# Digital_Outputs.net
KiCad netlist of a schematic drawn in Altium Designer
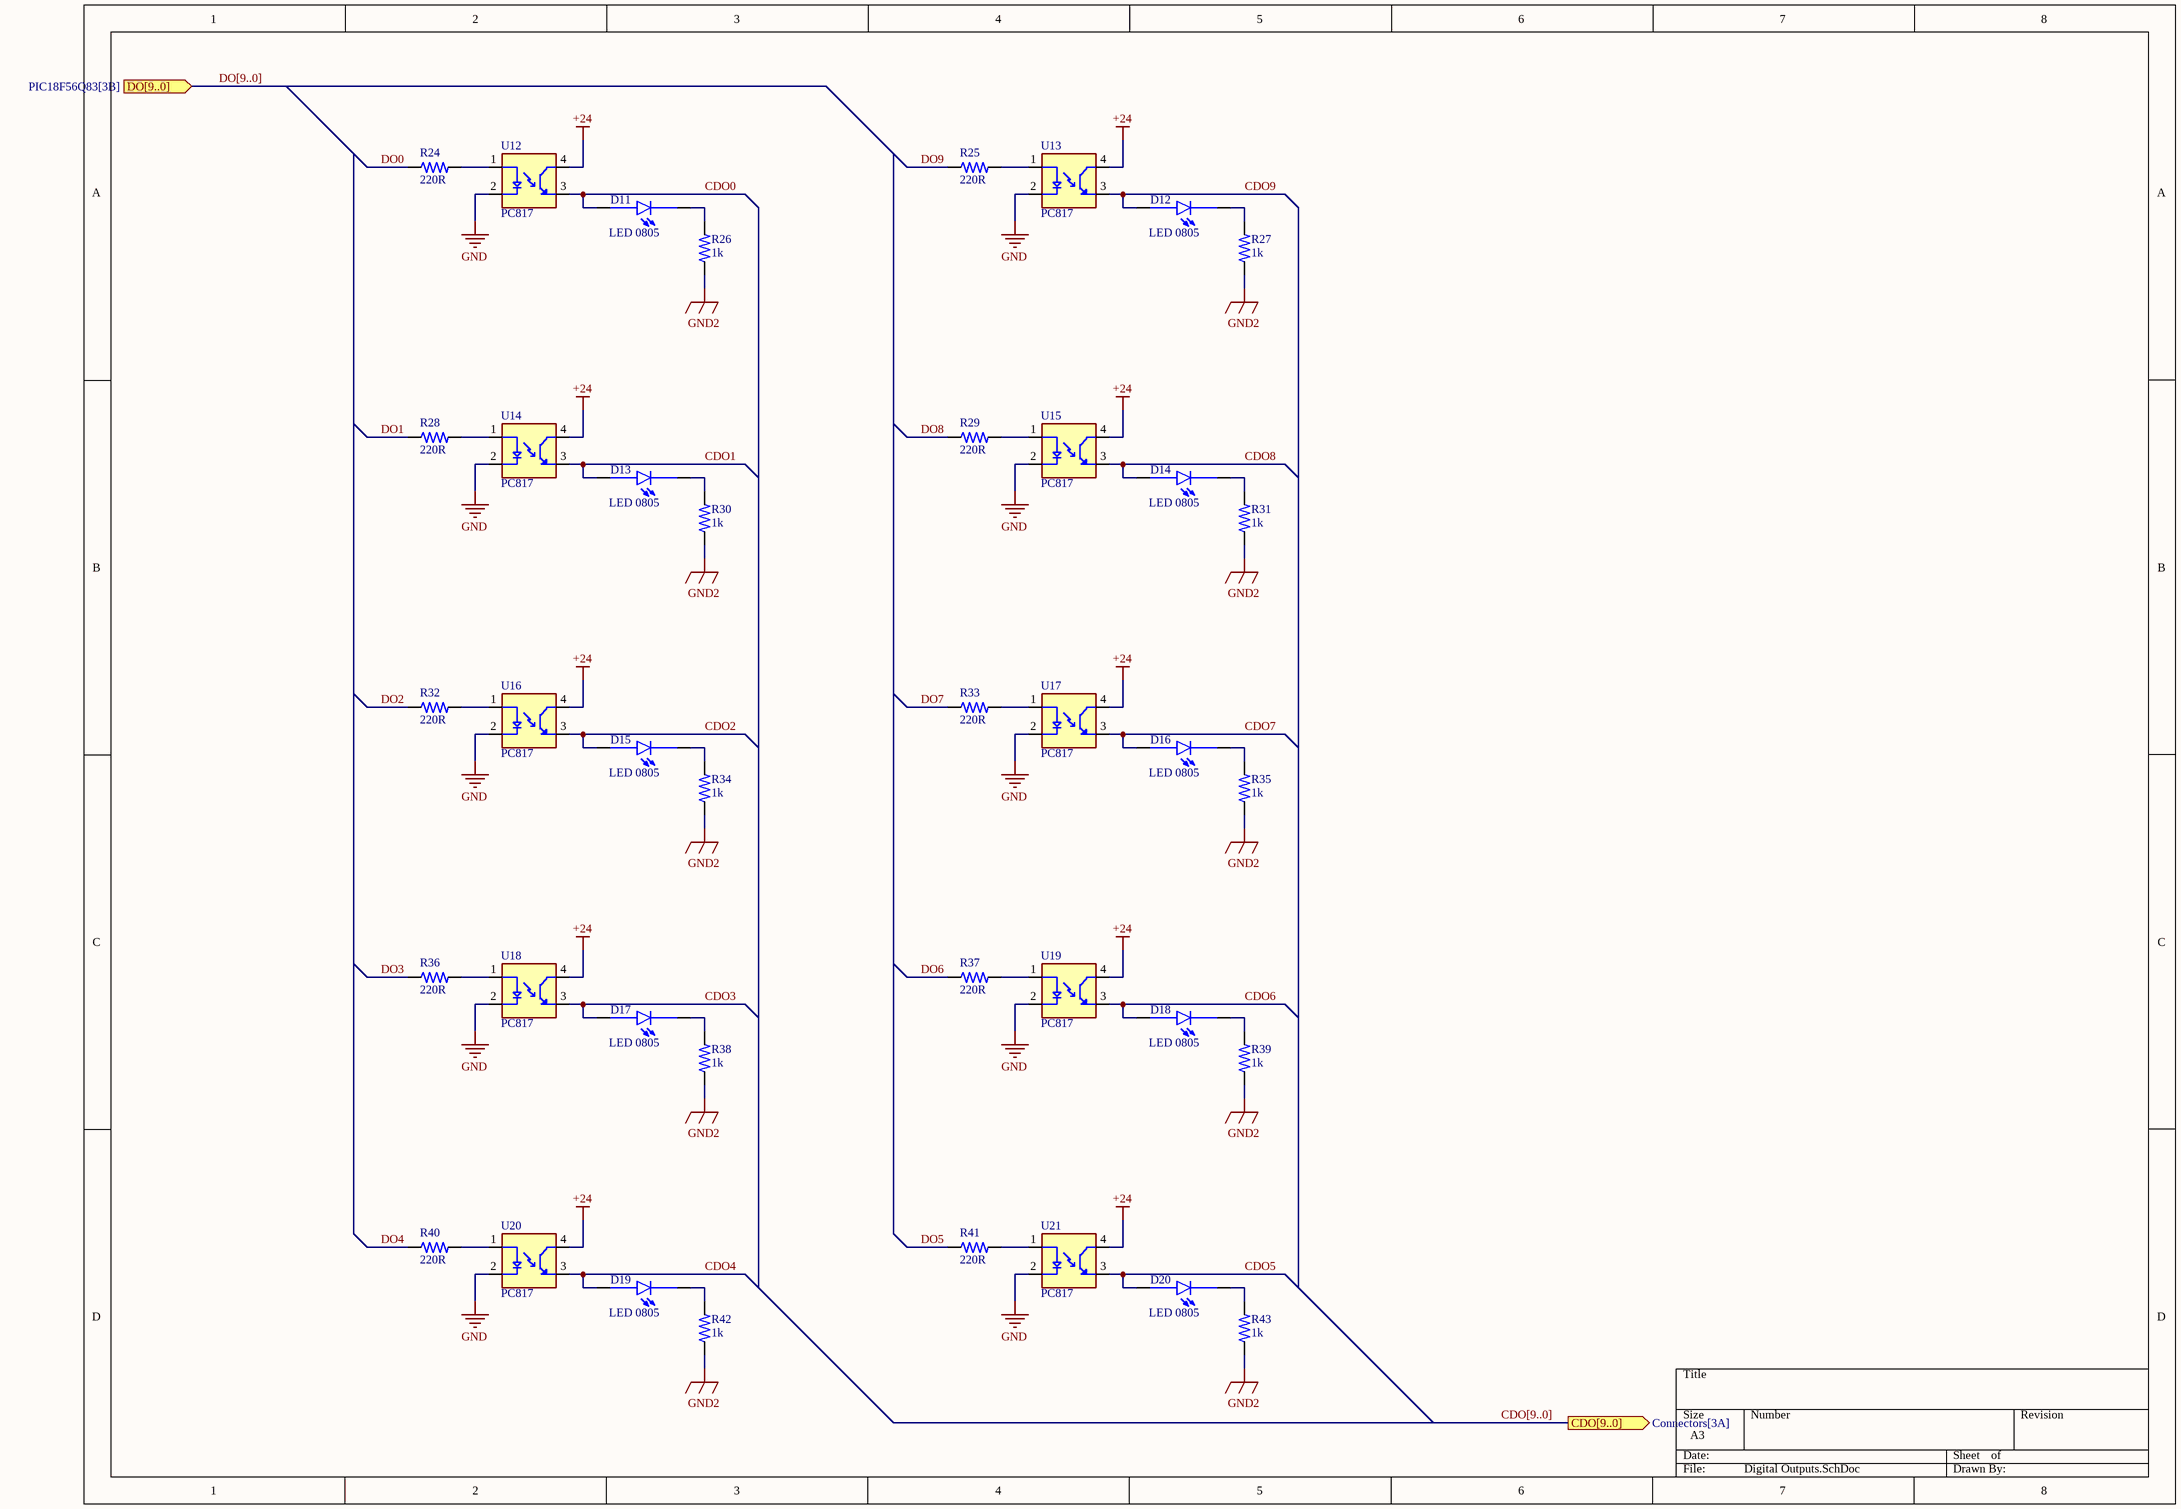
[diagram p0: Digital Outputs.SchDoc]

(export (version "E")
  (design (tool "Eeschema 10.0.6"))
  (components
    (comp (ref "D11")
      (value "LED 0805")
      (footprint "LED 0805")
      (description "LED Uni-Color Green 4-Pin Chip 0805 T/R")
      (fields (field (name "MP") "597-3305-607F"))
      (libsource (lib "LEDs SMD") (part "LED 0805"))
    )
    (comp (ref "D12")
      (value "LED 0805")
      (footprint "LED 0805")
      (description "LED Uni-Color Green 4-Pin Chip 0805 T/R")
      (fields (field (name "MP") "597-3305-607F"))
      (libsource (lib "LEDs SMD") (part "LED 0805"))
    )
    (comp (ref "D13")
      (value "LED 0805")
      (footprint "LED 0805")
      (description "LED Uni-Color Green 4-Pin Chip 0805 T/R")
      (fields (field (name "MP") "597-3305-607F"))
      (libsource (lib "LEDs SMD") (part "LED 0805"))
    )
    (comp (ref "D14")
      (value "LED 0805")
      (footprint "LED 0805")
      (description "LED Uni-Color Green 4-Pin Chip 0805 T/R")
      (fields (field (name "MP") "597-3305-607F"))
      (libsource (lib "LEDs SMD") (part "LED 0805"))
    )
    (comp (ref "D15")
      (value "LED 0805")
      (footprint "LED 0805")
      (description "LED Uni-Color Green 4-Pin Chip 0805 T/R")
      (fields (field (name "MP") "597-3305-607F"))
      (libsource (lib "LEDs SMD") (part "LED 0805"))
    )
    (comp (ref "D16")
      (value "LED 0805")
      (footprint "LED 0805")
      (description "LED Uni-Color Green 4-Pin Chip 0805 T/R")
      (fields (field (name "MP") "597-3305-607F"))
      (libsource (lib "LEDs SMD") (part "LED 0805"))
    )
    (comp (ref "D17")
      (value "LED 0805")
      (footprint "LED 0805")
      (description "LED Uni-Color Green 4-Pin Chip 0805 T/R")
      (fields (field (name "MP") "597-3305-607F"))
      (libsource (lib "LEDs SMD") (part "LED 0805"))
    )
    (comp (ref "D18")
      (value "LED 0805")
      (footprint "LED 0805")
      (description "LED Uni-Color Green 4-Pin Chip 0805 T/R")
      (fields (field (name "MP") "597-3305-607F"))
      (libsource (lib "LEDs SMD") (part "LED 0805"))
    )
    (comp (ref "D19")
      (value "LED 0805")
      (footprint "LED 0805")
      (description "LED Uni-Color Green 4-Pin Chip 0805 T/R")
      (fields (field (name "MP") "597-3305-607F"))
      (libsource (lib "LEDs SMD") (part "LED 0805"))
    )
    (comp (ref "D20")
      (value "LED 0805")
      (footprint "LED 0805")
      (description "LED Uni-Color Green 4-Pin Chip 0805 T/R")
      (fields (field (name "MP") "597-3305-607F"))
      (libsource (lib "LEDs SMD") (part "LED 0805"))
    )
    (comp (ref "R24")
      (value "220R")
      (footprint "0805")
      (fields
        (field (name "MP") "2-2176053-0")
        (field (name "TOLERANCE") "1%")
        (field (name "MF") "TE Connectivity")
      )
      (libsource (lib "Resistors SMD") (part "0805_Resistor"))
    )
    (comp (ref "R25")
      (value "220R")
      (footprint "0805")
      (fields
        (field (name "MP") "2-2176053-0")
        (field (name "TOLERANCE") "1%")
        (field (name "MF") "TE Connectivity")
      )
      (libsource (lib "Resistors SMD") (part "0805_Resistor"))
    )
    (comp (ref "R26")
      (value "1k")
      (footprint "0805")
      (fields
        (field (name "MP") "2-2176053-0")
        (field (name "TOLERANCE") "1%")
        (field (name "MF") "TE Connectivity")
      )
      (libsource (lib "Resistors SMD") (part "0805_Resistor"))
    )
    (comp (ref "R27")
      (value "1k")
      (footprint "0805")
      (fields
        (field (name "MP") "2-2176053-0")
        (field (name "TOLERANCE") "1%")
        (field (name "MF") "TE Connectivity")
      )
      (libsource (lib "Resistors SMD") (part "0805_Resistor"))
    )
    (comp (ref "R28")
      (value "220R")
      (footprint "0805")
      (fields
        (field (name "MP") "2-2176053-0")
        (field (name "TOLERANCE") "1%")
        (field (name "MF") "TE Connectivity")
      )
      (libsource (lib "Resistors SMD") (part "0805_Resistor"))
    )
    (comp (ref "R29")
      (value "220R")
      (footprint "0805")
      (fields
        (field (name "MP") "2-2176053-0")
        (field (name "TOLERANCE") "1%")
        (field (name "MF") "TE Connectivity")
      )
      (libsource (lib "Resistors SMD") (part "0805_Resistor"))
    )
    (comp (ref "R30")
      (value "1k")
      (footprint "0805")
      (fields
        (field (name "MP") "2-2176053-0")
        (field (name "TOLERANCE") "1%")
        (field (name "MF") "TE Connectivity")
      )
      (libsource (lib "Resistors SMD") (part "0805_Resistor"))
    )
    (comp (ref "R31")
      (value "1k")
      (footprint "0805")
      (fields
        (field (name "MP") "2-2176053-0")
        (field (name "TOLERANCE") "1%")
        (field (name "MF") "TE Connectivity")
      )
      (libsource (lib "Resistors SMD") (part "0805_Resistor"))
    )
    (comp (ref "R32")
      (value "220R")
      (footprint "0805")
      (fields
        (field (name "MP") "2-2176053-0")
        (field (name "TOLERANCE") "1%")
        (field (name "MF") "TE Connectivity")
      )
      (libsource (lib "Resistors SMD") (part "0805_Resistor"))
    )
    (comp (ref "R33")
      (value "220R")
      (footprint "0805")
      (fields
        (field (name "MP") "2-2176053-0")
        (field (name "TOLERANCE") "1%")
        (field (name "MF") "TE Connectivity")
      )
      (libsource (lib "Resistors SMD") (part "0805_Resistor"))
    )
    (comp (ref "R34")
      (value "1k")
      (footprint "0805")
      (fields
        (field (name "MP") "2-2176053-0")
        (field (name "TOLERANCE") "1%")
        (field (name "MF") "TE Connectivity")
      )
      (libsource (lib "Resistors SMD") (part "0805_Resistor"))
    )
    (comp (ref "R35")
      (value "1k")
      (footprint "0805")
      (fields
        (field (name "MP") "2-2176053-0")
        (field (name "TOLERANCE") "1%")
        (field (name "MF") "TE Connectivity")
      )
      (libsource (lib "Resistors SMD") (part "0805_Resistor"))
    )
    (comp (ref "R36")
      (value "220R")
      (footprint "0805")
      (fields
        (field (name "MP") "2-2176053-0")
        (field (name "TOLERANCE") "1%")
        (field (name "MF") "TE Connectivity")
      )
      (libsource (lib "Resistors SMD") (part "0805_Resistor"))
    )
    (comp (ref "R37")
      (value "220R")
      (footprint "0805")
      (fields
        (field (name "MP") "2-2176053-0")
        (field (name "TOLERANCE") "1%")
        (field (name "MF") "TE Connectivity")
      )
      (libsource (lib "Resistors SMD") (part "0805_Resistor"))
    )
    (comp (ref "R38")
      (value "1k")
      (footprint "0805")
      (fields
        (field (name "MP") "2-2176053-0")
        (field (name "TOLERANCE") "1%")
        (field (name "MF") "TE Connectivity")
      )
      (libsource (lib "Resistors SMD") (part "0805_Resistor"))
    )
    (comp (ref "R39")
      (value "1k")
      (footprint "0805")
      (fields
        (field (name "MP") "2-2176053-0")
        (field (name "TOLERANCE") "1%")
        (field (name "MF") "TE Connectivity")
      )
      (libsource (lib "Resistors SMD") (part "0805_Resistor"))
    )
    (comp (ref "R40")
      (value "220R")
      (footprint "0805")
      (fields
        (field (name "MP") "2-2176053-0")
        (field (name "TOLERANCE") "1%")
        (field (name "MF") "TE Connectivity")
      )
      (libsource (lib "Resistors SMD") (part "0805_Resistor"))
    )
    (comp (ref "R41")
      (value "220R")
      (footprint "0805")
      (fields
        (field (name "MP") "2-2176053-0")
        (field (name "TOLERANCE") "1%")
        (field (name "MF") "TE Connectivity")
      )
      (libsource (lib "Resistors SMD") (part "0805_Resistor"))
    )
    (comp (ref "R42")
      (value "1k")
      (footprint "0805")
      (fields
        (field (name "MP") "2-2176053-0")
        (field (name "TOLERANCE") "1%")
        (field (name "MF") "TE Connectivity")
      )
      (libsource (lib "Resistors SMD") (part "0805_Resistor"))
    )
    (comp (ref "R43")
      (value "1k")
      (footprint "0805")
      (fields
        (field (name "MP") "2-2176053-0")
        (field (name "TOLERANCE") "1%")
        (field (name "MF") "TE Connectivity")
      )
      (libsource (lib "Resistors SMD") (part "0805_Resistor"))
    )
    (comp (ref "U12")
      (value "PC817")
      (footprint "PC817")
      (description "Optoisolator Transistor Output 5000Vrms 1 Channel 4-SMD")
      (fields (field (name "MP") "PC817XI") (field (name "MF") "Sharp Microelectronics"))
      (libsource (lib "Optocoupler SMD") (part "PC817"))
    )
    (comp (ref "U13")
      (value "PC817")
      (footprint "PC817")
      (description "Optoisolator Transistor Output 5000Vrms 1 Channel 4-SMD")
      (fields (field (name "MP") "PC817XI") (field (name "MF") "Sharp Microelectronics"))
      (libsource (lib "Optocoupler SMD") (part "PC817"))
    )
    (comp (ref "U14")
      (value "PC817")
      (footprint "PC817")
      (description "Optoisolator Transistor Output 5000Vrms 1 Channel 4-SMD")
      (fields (field (name "MP") "PC817XI") (field (name "MF") "Sharp Microelectronics"))
      (libsource (lib "Optocoupler SMD") (part "PC817"))
    )
    (comp (ref "U15")
      (value "PC817")
      (footprint "PC817")
      (description "Optoisolator Transistor Output 5000Vrms 1 Channel 4-SMD")
      (fields (field (name "MP") "PC817XI") (field (name "MF") "Sharp Microelectronics"))
      (libsource (lib "Optocoupler SMD") (part "PC817"))
    )
    (comp (ref "U16")
      (value "PC817")
      (footprint "PC817")
      (description "Optoisolator Transistor Output 5000Vrms 1 Channel 4-SMD")
      (fields (field (name "MP") "PC817XI") (field (name "MF") "Sharp Microelectronics"))
      (libsource (lib "Optocoupler SMD") (part "PC817"))
    )
    (comp (ref "U17")
      (value "PC817")
      (footprint "PC817")
      (description "Optoisolator Transistor Output 5000Vrms 1 Channel 4-SMD")
      (fields (field (name "MP") "PC817XI") (field (name "MF") "Sharp Microelectronics"))
      (libsource (lib "Optocoupler SMD") (part "PC817"))
    )
    (comp (ref "U18")
      (value "PC817")
      (footprint "PC817")
      (description "Optoisolator Transistor Output 5000Vrms 1 Channel 4-SMD")
      (fields (field (name "MP") "PC817XI") (field (name "MF") "Sharp Microelectronics"))
      (libsource (lib "Optocoupler SMD") (part "PC817"))
    )
    (comp (ref "U19")
      (value "PC817")
      (footprint "PC817")
      (description "Optoisolator Transistor Output 5000Vrms 1 Channel 4-SMD")
      (fields (field (name "MP") "PC817XI") (field (name "MF") "Sharp Microelectronics"))
      (libsource (lib "Optocoupler SMD") (part "PC817"))
    )
    (comp (ref "U20")
      (value "PC817")
      (footprint "PC817")
      (description "Optoisolator Transistor Output 5000Vrms 1 Channel 4-SMD")
      (fields (field (name "MP") "PC817XI") (field (name "MF") "Sharp Microelectronics"))
      (libsource (lib "Optocoupler SMD") (part "PC817"))
    )
    (comp (ref "U21")
      (value "PC817")
      (footprint "PC817")
      (description "Optoisolator Transistor Output 5000Vrms 1 Channel 4-SMD")
      (fields (field (name "MP") "PC817XI") (field (name "MF") "Sharp Microelectronics"))
      (libsource (lib "Optocoupler SMD") (part "PC817"))
    )
  )
  (nets
    (net (code "1") (name "+24") (class "Default")
      (node (ref "U12") (pin "4") (pinfunction "CT_4") (pintype "passive"))
      (node (ref "U13") (pin "4") (pinfunction "CT_4") (pintype "passive"))
      (node (ref "U14") (pin "4") (pinfunction "CT_4") (pintype "passive"))
      (node (ref "U15") (pin "4") (pinfunction "CT_4") (pintype "passive"))
      (node (ref "U16") (pin "4") (pinfunction "CT_4") (pintype "passive"))
      (node (ref "U17") (pin "4") (pinfunction "CT_4") (pintype "passive"))
      (node (ref "U18") (pin "4") (pinfunction "CT_4") (pintype "passive"))
      (node (ref "U19") (pin "4") (pinfunction "CT_4") (pintype "passive"))
      (node (ref "U20") (pin "4") (pinfunction "CT_4") (pintype "passive"))
      (node (ref "U21") (pin "4") (pinfunction "CT_4") (pintype "passive"))
    )
    (net (code "2") (name "/CDO0") (class "Default")
      (node (ref "D11") (pin "A") (pinfunction "A_A") (pintype "passive"))
      (node (ref "U12") (pin "3") (pinfunction "ET_3") (pintype "passive"))
    )
    (net (code "3") (name "/CDO1") (class "Default")
      (node (ref "D13") (pin "A") (pinfunction "A_A") (pintype "passive"))
      (node (ref "U14") (pin "3") (pinfunction "ET_3") (pintype "passive"))
    )
    (net (code "4") (name "/CDO2") (class "Default")
      (node (ref "D15") (pin "A") (pinfunction "A_A") (pintype "passive"))
      (node (ref "U16") (pin "3") (pinfunction "ET_3") (pintype "passive"))
    )
    (net (code "5") (name "/CDO3") (class "Default")
      (node (ref "D17") (pin "A") (pinfunction "A_A") (pintype "passive"))
      (node (ref "U18") (pin "3") (pinfunction "ET_3") (pintype "passive"))
    )
    (net (code "6") (name "/CDO4") (class "Default")
      (node (ref "D19") (pin "A") (pinfunction "A_A") (pintype "passive"))
      (node (ref "U20") (pin "3") (pinfunction "ET_3") (pintype "passive"))
    )
    (net (code "7") (name "/CDO5") (class "Default")
      (node (ref "D20") (pin "A") (pinfunction "A_A") (pintype "passive"))
      (node (ref "U21") (pin "3") (pinfunction "ET_3") (pintype "passive"))
    )
    (net (code "8") (name "/CDO6") (class "Default")
      (node (ref "D18") (pin "A") (pinfunction "A_A") (pintype "passive"))
      (node (ref "U19") (pin "3") (pinfunction "ET_3") (pintype "passive"))
    )
    (net (code "9") (name "/CDO7") (class "Default")
      (node (ref "D16") (pin "A") (pinfunction "A_A") (pintype "passive"))
      (node (ref "U17") (pin "3") (pinfunction "ET_3") (pintype "passive"))
    )
    (net (code "10") (name "/CDO8") (class "Default")
      (node (ref "D14") (pin "A") (pinfunction "A_A") (pintype "passive"))
      (node (ref "U15") (pin "3") (pinfunction "ET_3") (pintype "passive"))
    )
    (net (code "11") (name "/CDO9") (class "Default")
      (node (ref "D12") (pin "A") (pinfunction "A_A") (pintype "passive"))
      (node (ref "U13") (pin "3") (pinfunction "ET_3") (pintype "passive"))
    )
    (net (code "13") (name "/DO0") (class "Default")
      (node (ref "R24") (pin "1") (pinfunction "1_1") (pintype "passive"))
    )
    (net (code "14") (name "/DO1") (class "Default")
      (node (ref "R28") (pin "1") (pinfunction "1_1") (pintype "passive"))
    )
    (net (code "15") (name "/DO2") (class "Default")
      (node (ref "R32") (pin "1") (pinfunction "1_1") (pintype "passive"))
    )
    (net (code "16") (name "/DO3") (class "Default")
      (node (ref "R36") (pin "1") (pinfunction "1_1") (pintype "passive"))
    )
    (net (code "17") (name "/DO4") (class "Default")
      (node (ref "R40") (pin "1") (pinfunction "1_1") (pintype "passive"))
    )
    (net (code "18") (name "/DO5") (class "Default")
      (node (ref "R41") (pin "1") (pinfunction "1_1") (pintype "passive"))
    )
    (net (code "19") (name "/DO6") (class "Default")
      (node (ref "R37") (pin "1") (pinfunction "1_1") (pintype "passive"))
    )
    (net (code "20") (name "/DO7") (class "Default")
      (node (ref "R33") (pin "1") (pinfunction "1_1") (pintype "passive"))
    )
    (net (code "21") (name "/DO8") (class "Default")
      (node (ref "R29") (pin "1") (pinfunction "1_1") (pintype "passive"))
    )
    (net (code "22") (name "/DO9") (class "Default")
      (node (ref "R25") (pin "1") (pinfunction "1_1") (pintype "passive"))
    )
    (net (code "24") (name "GND") (class "Default")
      (node (ref "U12") (pin "2") (pinfunction "C_2") (pintype "passive"))
      (node (ref "U13") (pin "2") (pinfunction "C_2") (pintype "passive"))
      (node (ref "U14") (pin "2") (pinfunction "C_2") (pintype "passive"))
      (node (ref "U15") (pin "2") (pinfunction "C_2") (pintype "passive"))
      (node (ref "U16") (pin "2") (pinfunction "C_2") (pintype "passive"))
      (node (ref "U17") (pin "2") (pinfunction "C_2") (pintype "passive"))
      (node (ref "U18") (pin "2") (pinfunction "C_2") (pintype "passive"))
      (node (ref "U19") (pin "2") (pinfunction "C_2") (pintype "passive"))
      (node (ref "U20") (pin "2") (pinfunction "C_2") (pintype "passive"))
      (node (ref "U21") (pin "2") (pinfunction "C_2") (pintype "passive"))
    )
    (net (code "25") (name "GND2") (class "Default")
      (node (ref "R26") (pin "1") (pinfunction "1_1") (pintype "passive"))
      (node (ref "R27") (pin "1") (pinfunction "1_1") (pintype "passive"))
      (node (ref "R30") (pin "1") (pinfunction "1_1") (pintype "passive"))
      (node (ref "R31") (pin "1") (pinfunction "1_1") (pintype "passive"))
      (node (ref "R34") (pin "1") (pinfunction "1_1") (pintype "passive"))
      (node (ref "R35") (pin "1") (pinfunction "1_1") (pintype "passive"))
      (node (ref "R38") (pin "1") (pinfunction "1_1") (pintype "passive"))
      (node (ref "R39") (pin "1") (pinfunction "1_1") (pintype "passive"))
      (node (ref "R42") (pin "1") (pinfunction "1_1") (pintype "passive"))
      (node (ref "R43") (pin "1") (pinfunction "1_1") (pintype "passive"))
    )
    (net (code "26") (name "Net-(D11-PadC)") (class "Default")
      (node (ref "D11") (pin "C") (pinfunction "C_C") (pintype "passive"))
      (node (ref "R26") (pin "2") (pinfunction "2_2") (pintype "passive"))
    )
    (net (code "27") (name "Net-(D12-PadC)") (class "Default")
      (node (ref "D12") (pin "C") (pinfunction "C_C") (pintype "passive"))
      (node (ref "R27") (pin "2") (pinfunction "2_2") (pintype "passive"))
    )
    (net (code "28") (name "Net-(D13-PadC)") (class "Default")
      (node (ref "D13") (pin "C") (pinfunction "C_C") (pintype "passive"))
      (node (ref "R30") (pin "2") (pinfunction "2_2") (pintype "passive"))
    )
    (net (code "29") (name "Net-(D14-PadC)") (class "Default")
      (node (ref "D14") (pin "C") (pinfunction "C_C") (pintype "passive"))
      (node (ref "R31") (pin "2") (pinfunction "2_2") (pintype "passive"))
    )
    (net (code "30") (name "Net-(D15-PadC)") (class "Default")
      (node (ref "D15") (pin "C") (pinfunction "C_C") (pintype "passive"))
      (node (ref "R34") (pin "2") (pinfunction "2_2") (pintype "passive"))
    )
    (net (code "31") (name "Net-(D16-PadC)") (class "Default")
      (node (ref "D16") (pin "C") (pinfunction "C_C") (pintype "passive"))
      (node (ref "R35") (pin "2") (pinfunction "2_2") (pintype "passive"))
    )
    (net (code "32") (name "Net-(D17-PadC)") (class "Default")
      (node (ref "D17") (pin "C") (pinfunction "C_C") (pintype "passive"))
      (node (ref "R38") (pin "2") (pinfunction "2_2") (pintype "passive"))
    )
    (net (code "33") (name "Net-(D18-PadC)") (class "Default")
      (node (ref "D18") (pin "C") (pinfunction "C_C") (pintype "passive"))
      (node (ref "R39") (pin "2") (pinfunction "2_2") (pintype "passive"))
    )
    (net (code "34") (name "Net-(D19-PadC)") (class "Default")
      (node (ref "D19") (pin "C") (pinfunction "C_C") (pintype "passive"))
      (node (ref "R42") (pin "2") (pinfunction "2_2") (pintype "passive"))
    )
    (net (code "35") (name "Net-(D20-PadC)") (class "Default")
      (node (ref "D20") (pin "C") (pinfunction "C_C") (pintype "passive"))
      (node (ref "R43") (pin "2") (pinfunction "2_2") (pintype "passive"))
    )
    (net (code "36") (name "Net-(U12-A)") (class "Default")
      (node (ref "R24") (pin "2") (pinfunction "2_2") (pintype "passive"))
      (node (ref "U12") (pin "1") (pinfunction "A_1") (pintype "passive"))
    )
    (net (code "37") (name "Net-(U13-A)") (class "Default")
      (node (ref "R25") (pin "2") (pinfunction "2_2") (pintype "passive"))
      (node (ref "U13") (pin "1") (pinfunction "A_1") (pintype "passive"))
    )
    (net (code "38") (name "Net-(U14-A)") (class "Default")
      (node (ref "R28") (pin "2") (pinfunction "2_2") (pintype "passive"))
      (node (ref "U14") (pin "1") (pinfunction "A_1") (pintype "passive"))
    )
    (net (code "39") (name "Net-(U15-A)") (class "Default")
      (node (ref "R29") (pin "2") (pinfunction "2_2") (pintype "passive"))
      (node (ref "U15") (pin "1") (pinfunction "A_1") (pintype "passive"))
    )
    (net (code "40") (name "Net-(U16-A)") (class "Default")
      (node (ref "R32") (pin "2") (pinfunction "2_2") (pintype "passive"))
      (node (ref "U16") (pin "1") (pinfunction "A_1") (pintype "passive"))
    )
    (net (code "41") (name "Net-(U17-A)") (class "Default")
      (node (ref "R33") (pin "2") (pinfunction "2_2") (pintype "passive"))
      (node (ref "U17") (pin "1") (pinfunction "A_1") (pintype "passive"))
    )
    (net (code "42") (name "Net-(U18-A)") (class "Default")
      (node (ref "R36") (pin "2") (pinfunction "2_2") (pintype "passive"))
      (node (ref "U18") (pin "1") (pinfunction "A_1") (pintype "passive"))
    )
    (net (code "43") (name "Net-(U19-A)") (class "Default")
      (node (ref "R37") (pin "2") (pinfunction "2_2") (pintype "passive"))
      (node (ref "U19") (pin "1") (pinfunction "A_1") (pintype "passive"))
    )
    (net (code "44") (name "Net-(U20-A)") (class "Default")
      (node (ref "R40") (pin "2") (pinfunction "2_2") (pintype "passive"))
      (node (ref "U20") (pin "1") (pinfunction "A_1") (pintype "passive"))
    )
    (net (code "45") (name "Net-(U21-A)") (class "Default")
      (node (ref "R41") (pin "2") (pinfunction "2_2") (pintype "passive"))
      (node (ref "U21") (pin "1") (pinfunction "A_1") (pintype "passive"))
    )
  )
)
